# MotorDriver.net
KiCad netlist of a schematic drawn in Altium Designer
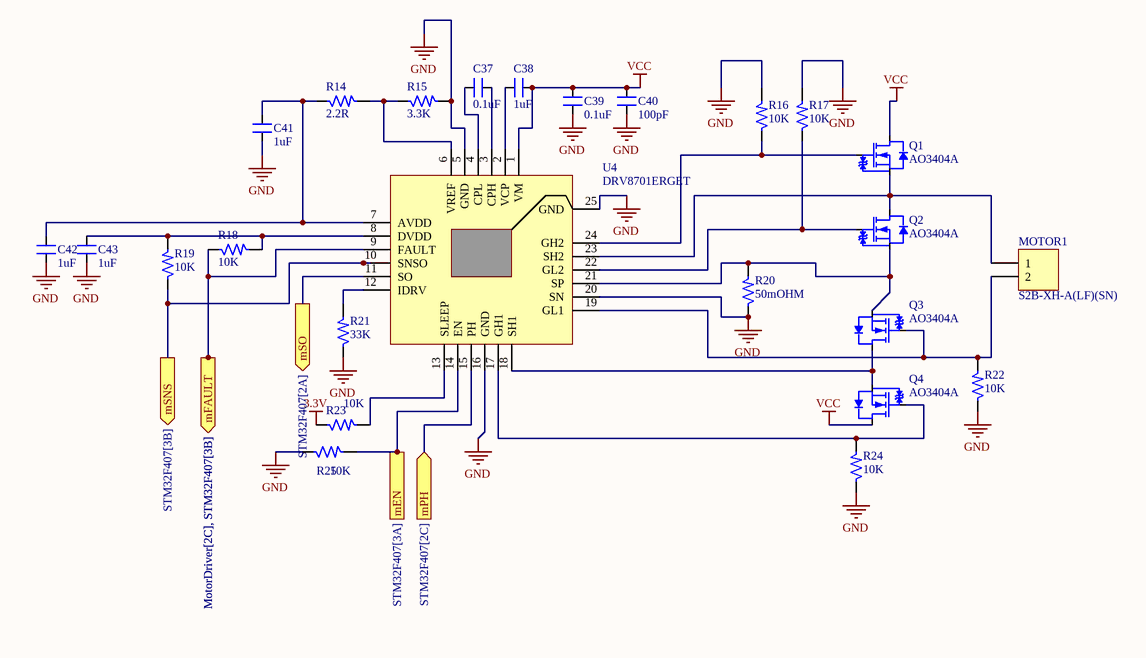
[diagram p0: MotorDriver.SchDoc]

(export (version "E")
  (design (tool "Eeschema 10.0.6"))
  (components
    (comp (ref "C37")
      (value "0.1uF")
      (footprint "CAP_0805")
      (description "0.1µF ±20% 50V Ceramic Capacitor X7R 0805 (2012 Metric)")
      (fields
        (field (name "MANUFACTURER") "Samsung Electro-Mechanics")
        (field (name "MANUFACTURER PART NUMBER") "CL21B104MBCNNNC")
      )
      (libsource (lib "ESTEEMPCBLIB") (part "CAP_0.1uF-50V-20%-0805"))
    )
    (comp (ref "C38")
      (value "1uF")
      (footprint "CAP_0805")
      (description "1µF ±5% 50V Ceramic Capacitor X7R 0805 (2012 Metric)")
      (fields
        (field (name "MANUFACTURER") "Samsung")
        (field (name "MANUFACTURER PART NUMBER") "CC0805JKX7R9BB105")
      )
      (libsource (lib "ESTEEMPCBLIB") (part "CAP_1uF-50V-5%-0805"))
    )
    (comp (ref "C39")
      (value "0.1uF")
      (footprint "CAP_0805")
      (description "0.1µF ±20% 50V Ceramic Capacitor X7R 0805 (2012 Metric)")
      (fields
        (field (name "MANUFACTURER") "Samsung Electro-Mechanics")
        (field (name "MANUFACTURER PART NUMBER") "CL21B104MBCNNNC")
      )
      (libsource (lib "ESTEEMPCBLIB") (part "CAP_0.1uF-50V-20%-0805"))
    )
    (comp (ref "C40")
      (value "100pF")
      (footprint "CAP_0805")
      (description "100pF ±5% 100V Ceramic Capacitor C0G, NP0 0805 (2012 Metric)")
      (fields
        (field (name "MANUFACTURER") "Murata")
        (field (name "MANUFACTURER PART NUMBER") "CL21C101JC61PNC")
      )
      (libsource (lib "ESTEEMPCBLIB") (part "CAP_100pF-100V-5%-0805"))
    )
    (comp (ref "C41")
      (value "1uF")
      (footprint "CAP_0805")
      (description "1µF ±5% 50V Ceramic Capacitor X7R 0805 (2012 Metric)")
      (fields
        (field (name "MANUFACTURER") "Samsung")
        (field (name "MANUFACTURER PART NUMBER") "CC0805JKX7R9BB105")
      )
      (libsource (lib "ESTEEMPCBLIB") (part "CAP_1uF-50V-5%-0805"))
    )
    (comp (ref "C42")
      (value "1uF")
      (footprint "CAP_0805")
      (description "1µF ±5% 50V Ceramic Capacitor X7R 0805 (2012 Metric)")
      (fields
        (field (name "MANUFACTURER") "Samsung")
        (field (name "MANUFACTURER PART NUMBER") "CC0805JKX7R9BB105")
      )
      (libsource (lib "ESTEEMPCBLIB") (part "CAP_1uF-50V-5%-0805"))
    )
    (comp (ref "C43")
      (value "1uF")
      (footprint "CAP_0805")
      (description "1µF ±5% 50V Ceramic Capacitor X7R 0805 (2012 Metric)")
      (fields
        (field (name "MANUFACTURER") "Samsung")
        (field (name "MANUFACTURER PART NUMBER") "CC0805JKX7R9BB105")
      )
      (libsource (lib "ESTEEMPCBLIB") (part "CAP_1uF-50V-5%-0805"))
    )
    (comp (ref "MOTOR1")
      (value "S2B-XH-A(LF)(SN)")
      (footprint "CON2_100_S2B-XH-A_TH_RA")
      (description "2 Pins, 1 Row 2.54mm Pitch, right angle Connector, male")
      (fields (field (name "MANUFACTURER") "JST") (field (name "MATING PART NUMBER") "XHP-2"))
      (libsource (lib "ESTEEMPCBLIB") (part "CON-PLG_2X1-100-RA-TH"))
    )
    (comp (ref "Q1")
      (value "AO3404A")
      (footprint "SOT 23-3")
      (description "N-Channel 30V 5.8A (Ta) 1.4W (Ta) Surface Mount SOT-23-3L")
      (fields (field (name "MANUFACTURER") "International Rectifier"))
      (libsource (lib "ESTEEMPCBLIB") (part "MOSFET-N_30V-5.8A-SOT23"))
    )
    (comp (ref "Q2")
      (value "AO3404A")
      (footprint "SOT 23-3")
      (description "N-Channel 30V 5.8A (Ta) 1.4W (Ta) Surface Mount SOT-23-3L")
      (fields (field (name "MANUFACTURER") "International Rectifier"))
      (libsource (lib "ESTEEMPCBLIB") (part "MOSFET-N_30V-5.8A-SOT23"))
    )
    (comp (ref "Q3")
      (value "AO3404A")
      (footprint "SOT 23-3")
      (description "N-Channel 30V 5.8A (Ta) 1.4W (Ta) Surface Mount SOT-23-3L")
      (fields (field (name "MANUFACTURER") "International Rectifier"))
      (libsource (lib "ESTEEMPCBLIB") (part "MOSFET-N_30V-5.8A-SOT23"))
    )
    (comp (ref "Q4")
      (value "AO3404A")
      (footprint "SOT 23-3")
      (description "N-Channel 30V 5.8A (Ta) 1.4W (Ta) Surface Mount SOT-23-3L")
      (fields (field (name "MANUFACTURER") "International Rectifier"))
      (libsource (lib "ESTEEMPCBLIB") (part "MOSFET-N_30V-5.8A-SOT23"))
    )
    (comp (ref "R14")
      (value "2.2R")
      (footprint "RES_0603")
      (fields
        (field (name "MANUFACTURER") "Panasonic Electronic Components")
        (field (name "MANUFACTURER PART NUMBER") "ERJ-3RQF2R2V")
      )
      (libsource (lib "ESTEEMPCBLIB") (part "RES_2.2R-0.1W-1%-0603"))
    )
    (comp (ref "R15")
      (value "3.3K")
      (footprint "RES_0805")
      (description "3.3 kOhms ±1% 0.125W, 1/8W Chip Resistor 0805 (2012 Metric) Thick Film")
      (fields (field (name "MANUFACTURER") "Panasonic") (field (name "MANUFACTURER PART NUMBER") "1623214-1"))
      (libsource (lib "ESTEEMPCBLIB") (part "RES_3.3K-0.125W-1%-0805"))
    )
    (comp (ref "R16")
      (value "10K")
      (footprint "RES_0805")
      (description "10 kOhms ±1% 0.125W, 1/8W Chip Resistor 0805 (2012 Metric) Automotive AEC-Q200 Thick Film")
      (fields (field (name "MANUFACTURER") "CTS") (field (name "MANUFACTURER PART NUMBER") "WR08X1002FTL"))
      (libsource (lib "ESTEEMPCBLIB") (part "RES_10K-0.125W-1%-0805"))
    )
    (comp (ref "R17")
      (value "10K")
      (footprint "RES_0805")
      (description "10 kOhms ±1% 0.125W, 1/8W Chip Resistor 0805 (2012 Metric) Automotive AEC-Q200 Thick Film")
      (fields (field (name "MANUFACTURER") "CTS") (field (name "MANUFACTURER PART NUMBER") "WR08X1002FTL"))
      (libsource (lib "ESTEEMPCBLIB") (part "RES_10K-0.125W-1%-0805"))
    )
    (comp (ref "R18")
      (value "10K")
      (footprint "RES_0805")
      (description "10 kOhms ±1% 0.125W, 1/8W Chip Resistor 0805 (2012 Metric) Automotive AEC-Q200 Thick Film")
      (fields (field (name "MANUFACTURER") "CTS") (field (name "MANUFACTURER PART NUMBER") "WR08X1002FTL"))
      (libsource (lib "ESTEEMPCBLIB") (part "RES_10K-0.125W-1%-0805"))
    )
    (comp (ref "R19")
      (value "10K")
      (footprint "RES_0805")
      (description "10 kOhms ±1% 0.125W, 1/8W Chip Resistor 0805 (2012 Metric) Automotive AEC-Q200 Thick Film")
      (fields (field (name "MANUFACTURER") "CTS") (field (name "MANUFACTURER PART NUMBER") "WR08X1002FTL"))
      (libsource (lib "ESTEEMPCBLIB") (part "RES_10K-0.125W-1%-0805"))
    )
    (comp (ref "R20")
      (value "50mOHM")
      (footprint "RES_2512")
      (fields
        (field (name "MANUFACTURER") "Yageo")
        (field (name "MANUFACTURER PART NUMBER") "PA2512FKF7W0R05E")
      )
      (libsource (lib "ESTEEMPCBLIB") (part "RES_50mOhm-2W-1%-2512"))
    )
    (comp (ref "R21")
      (value "33K")
      (footprint "RES_0805")
      (fields
        (field (name "MANUFACTURER") "Vishay BCcomponents")
        (field (name "MANUFACTURER PART NUMBER") "CRG0805F33K")
      )
      (libsource (lib "ESTEEMPCBLIB") (part "RES_33K-0.125W-1%-0805"))
    )
    (comp (ref "R22")
      (value "10K")
      (footprint "RES_0805")
      (description "10 kOhms ±1% 0.125W, 1/8W Chip Resistor 0805 (2012 Metric) Automotive AEC-Q200 Thick Film")
      (fields (field (name "MANUFACTURER") "CTS") (field (name "MANUFACTURER PART NUMBER") "WR08X1002FTL"))
      (libsource (lib "ESTEEMPCBLIB") (part "RES_10K-0.125W-1%-0805"))
    )
    (comp (ref "R23")
      (value "10K")
      (footprint "RES_0805")
      (description "10 kOhms ±1% 0.125W, 1/8W Chip Resistor 0805 (2012 Metric) Automotive AEC-Q200 Thick Film")
      (fields (field (name "MANUFACTURER") "CTS") (field (name "MANUFACTURER PART NUMBER") "WR08X1002FTL"))
      (libsource (lib "ESTEEMPCBLIB") (part "RES_10K-0.125W-1%-0805"))
    )
    (comp (ref "R24")
      (value "10K")
      (footprint "RES_0805")
      (description "10 kOhms ±1% 0.125W, 1/8W Chip Resistor 0805 (2012 Metric) Automotive AEC-Q200 Thick Film")
      (fields (field (name "MANUFACTURER") "CTS") (field (name "MANUFACTURER PART NUMBER") "WR08X1002FTL"))
      (libsource (lib "ESTEEMPCBLIB") (part "RES_10K-0.125W-1%-0805"))
    )
    (comp (ref "R25")
      (value "10K")
      (footprint "RES_0805")
      (description "10 kOhms ±1% 0.125W, 1/8W Chip Resistor 0805 (2012 Metric) Automotive AEC-Q200 Thick Film")
      (fields (field (name "MANUFACTURER") "CTS") (field (name "MANUFACTURER PART NUMBER") "WR08X1002FTL"))
      (libsource (lib "ESTEEMPCBLIB") (part "RES_10K-0.125W-1%-0805"))
    )
    (comp (ref "U4")
      (value "DRV8701ERGET")
      (footprint "VFQFN24_19.6_196_12X32_SMD_1")
      (description "Motor Driver Power MOSFET Parallel 24-VQFN (4x4)")
      (fields (field (name "MANUFACTURER") "Texas Instruments"))
      (libsource (lib "ESTEEMPCBLIB") (part "IC_DRV8701ERGET"))
    )
  )
  (nets
    (net (code "1") (name "/mEN") (class "Default")
      (node (ref "R25") (pin "2") (pinfunction "2_2") (pintype "passive"))
      (node (ref "U4") (pin "14") (pinfunction "EN_14") (pintype "passive"))
    )
    (net (code "2") (name "/mFAULT") (class "Default")
      (node (ref "R18") (pin "1") (pinfunction "1_1") (pintype "passive"))
      (node (ref "U4") (pin "9") (pinfunction "FAULT_9") (pintype "passive"))
    )
    (net (code "3") (name "/mPH") (class "Default")
      (node (ref "U4") (pin "15") (pinfunction "PH_15") (pintype "passive"))
    )
    (net (code "4") (name "/mSNS") (class "Default")
      (node (ref "R19") (pin "1") (pinfunction "1_1") (pintype "passive"))
      (node (ref "U4") (pin "10") (pinfunction "SNSO_10") (pintype "passive"))
    )
    (net (code "5") (name "/mSO") (class "Default")
      (node (ref "U4") (pin "11") (pinfunction "SO_11") (pintype "passive"))
    )
    (net (code "6") (name "3.3V") (class "Default")
      (node (ref "R23") (pin "1") (pinfunction "1_1") (pintype "passive"))
    )
    (net (code "7") (name "GND") (class "Default")
      (node (ref "C39") (pin "1") (pinfunction "1_1") (pintype "passive"))
      (node (ref "C40") (pin "1") (pinfunction "1_1") (pintype "passive"))
      (node (ref "C41") (pin "1") (pinfunction "1_1") (pintype "passive"))
      (node (ref "C42") (pin "1") (pinfunction "1_1") (pintype "passive"))
      (node (ref "C43") (pin "1") (pinfunction "1_1") (pintype "passive"))
      (node (ref "R15") (pin "2") (pinfunction "2_2") (pintype "passive"))
      (node (ref "R16") (pin "2") (pinfunction "2_2") (pintype "passive"))
      (node (ref "R17") (pin "2") (pinfunction "2_2") (pintype "passive"))
      (node (ref "R20") (pin "1") (pinfunction "1_1") (pintype "passive"))
      (node (ref "R21") (pin "1") (pinfunction "1_1") (pintype "passive"))
      (node (ref "R22") (pin "1") (pinfunction "1_1") (pintype "passive"))
      (node (ref "R24") (pin "1") (pinfunction "1_1") (pintype "passive"))
      (node (ref "R25") (pin "1") (pinfunction "1_1") (pintype "passive"))
      (node (ref "U4") (pin "16") (pinfunction "GND_16") (pintype "passive"))
      (node (ref "U4") (pin "20") (pinfunction "SN_20") (pintype "passive"))
      (node (ref "U4") (pin "25") (pinfunction "GND_25") (pintype "passive"))
      (node (ref "U4") (pin "5") (pinfunction "GND_5") (pintype "passive"))
    )
    (net (code "8") (name "Net-(Q1-G)") (class "Default")
      (node (ref "Q1") (pin "1") (pinfunction "G_1") (pintype "passive"))
      (node (ref "R16") (pin "1") (pinfunction "1_1") (pintype "passive"))
      (node (ref "U4") (pin "24") (pinfunction "GH2_24") (pintype "passive"))
    )
    (net (code "9") (name "Net-(Q1-S)") (class "Default")
      (node (ref "MOTOR1") (pin "1") (pinfunction "1_1") (pintype "passive"))
      (node (ref "Q1") (pin "2") (pinfunction "S_2") (pintype "passive"))
      (node (ref "Q2") (pin "3") (pinfunction "D_3") (pintype "passive"))
      (node (ref "U4") (pin "23") (pinfunction "SH2_23") (pintype "passive"))
    )
    (net (code "10") (name "Net-(Q2-G)") (class "Default")
      (node (ref "Q2") (pin "1") (pinfunction "G_1") (pintype "passive"))
      (node (ref "R17") (pin "1") (pinfunction "1_1") (pintype "passive"))
      (node (ref "U4") (pin "22") (pinfunction "GL2_22") (pintype "passive"))
    )
    (net (code "11") (name "Net-(Q2-S)") (class "Default")
      (node (ref "Q2") (pin "2") (pinfunction "S_2") (pintype "passive"))
      (node (ref "Q3") (pin "2") (pinfunction "S_2") (pintype "passive"))
      (node (ref "R20") (pin "2") (pinfunction "2_2") (pintype "passive"))
      (node (ref "U4") (pin "21") (pinfunction "SP_21") (pintype "passive"))
    )
    (net (code "12") (name "Net-(Q3-D)") (class "Default")
      (node (ref "Q3") (pin "3") (pinfunction "D_3") (pintype "passive"))
      (node (ref "Q4") (pin "2") (pinfunction "S_2") (pintype "passive"))
      (node (ref "U4") (pin "18") (pinfunction "SH1_18") (pintype "passive"))
    )
    (net (code "13") (name "Net-(Q3-G)") (class "Default")
      (node (ref "MOTOR1") (pin "2") (pinfunction "2_2") (pintype "passive"))
      (node (ref "Q3") (pin "1") (pinfunction "G_1") (pintype "passive"))
      (node (ref "R22") (pin "2") (pinfunction "2_2") (pintype "passive"))
      (node (ref "U4") (pin "19") (pinfunction "GL1_19") (pintype "passive"))
    )
    (net (code "14") (name "Net-(Q4-G)") (class "Default")
      (node (ref "Q4") (pin "1") (pinfunction "G_1") (pintype "passive"))
      (node (ref "R24") (pin "2") (pinfunction "2_2") (pintype "passive"))
      (node (ref "U4") (pin "17") (pinfunction "GH1_17") (pintype "passive"))
    )
    (net (code "15") (name "Net-(U4-AVDD)") (class "Default")
      (node (ref "C41") (pin "2") (pinfunction "2_2") (pintype "passive"))
      (node (ref "C42") (pin "2") (pinfunction "2_2") (pintype "passive"))
      (node (ref "R14") (pin "1") (pinfunction "1_1") (pintype "passive"))
      (node (ref "U4") (pin "7") (pinfunction "AVDD_7") (pintype "passive"))
    )
    (net (code "16") (name "Net-(U4-CPH)") (class "Default")
      (node (ref "C37") (pin "1") (pinfunction "1_1") (pintype "passive"))
      (node (ref "U4") (pin "3") (pinfunction "CPH_3") (pintype "passive"))
    )
    (net (code "17") (name "Net-(U4-CPL)") (class "Default")
      (node (ref "C37") (pin "2") (pinfunction "2_2") (pintype "passive"))
      (node (ref "U4") (pin "4") (pinfunction "CPL_4") (pintype "passive"))
    )
    (net (code "18") (name "Net-(U4-DVDD)") (class "Default")
      (node (ref "C43") (pin "2") (pinfunction "2_2") (pintype "passive"))
      (node (ref "R18") (pin "2") (pinfunction "2_2") (pintype "passive"))
      (node (ref "R19") (pin "2") (pinfunction "2_2") (pintype "passive"))
      (node (ref "U4") (pin "8") (pinfunction "DVDD_8") (pintype "passive"))
    )
    (net (code "19") (name "Net-(U4-IDRV)") (class "Default")
      (node (ref "R21") (pin "2") (pinfunction "2_2") (pintype "passive"))
      (node (ref "U4") (pin "12") (pinfunction "IDRV_12") (pintype "passive"))
    )
    (net (code "20") (name "Net-(U4-SLEEP)") (class "Default")
      (node (ref "R23") (pin "2") (pinfunction "2_2") (pintype "passive"))
      (node (ref "U4") (pin "13") (pinfunction "SLEEP_13") (pintype "passive"))
    )
    (net (code "21") (name "Net-(U4-VCP)") (class "Default")
      (node (ref "C38") (pin "2") (pinfunction "2_2") (pintype "passive"))
      (node (ref "U4") (pin "2") (pinfunction "VCP_2") (pintype "passive"))
    )
    (net (code "22") (name "Net-(U4-VREF)") (class "Default")
      (node (ref "R14") (pin "2") (pinfunction "2_2") (pintype "passive"))
      (node (ref "R15") (pin "1") (pinfunction "1_1") (pintype "passive"))
      (node (ref "U4") (pin "6") (pinfunction "VREF_6") (pintype "passive"))
    )
    (net (code "23") (name "VCC") (class "Default")
      (node (ref "C38") (pin "1") (pinfunction "1_1") (pintype "passive"))
      (node (ref "C39") (pin "2") (pinfunction "2_2") (pintype "passive"))
      (node (ref "C40") (pin "2") (pinfunction "2_2") (pintype "passive"))
      (node (ref "Q1") (pin "3") (pinfunction "D_3") (pintype "passive"))
      (node (ref "Q4") (pin "3") (pinfunction "D_3") (pintype "passive"))
      (node (ref "U4") (pin "1") (pinfunction "VM_1") (pintype "passive"))
    )
  )
)
